# Controller_V2.net
KiCad netlist of a schematic drawn in Altium Designer
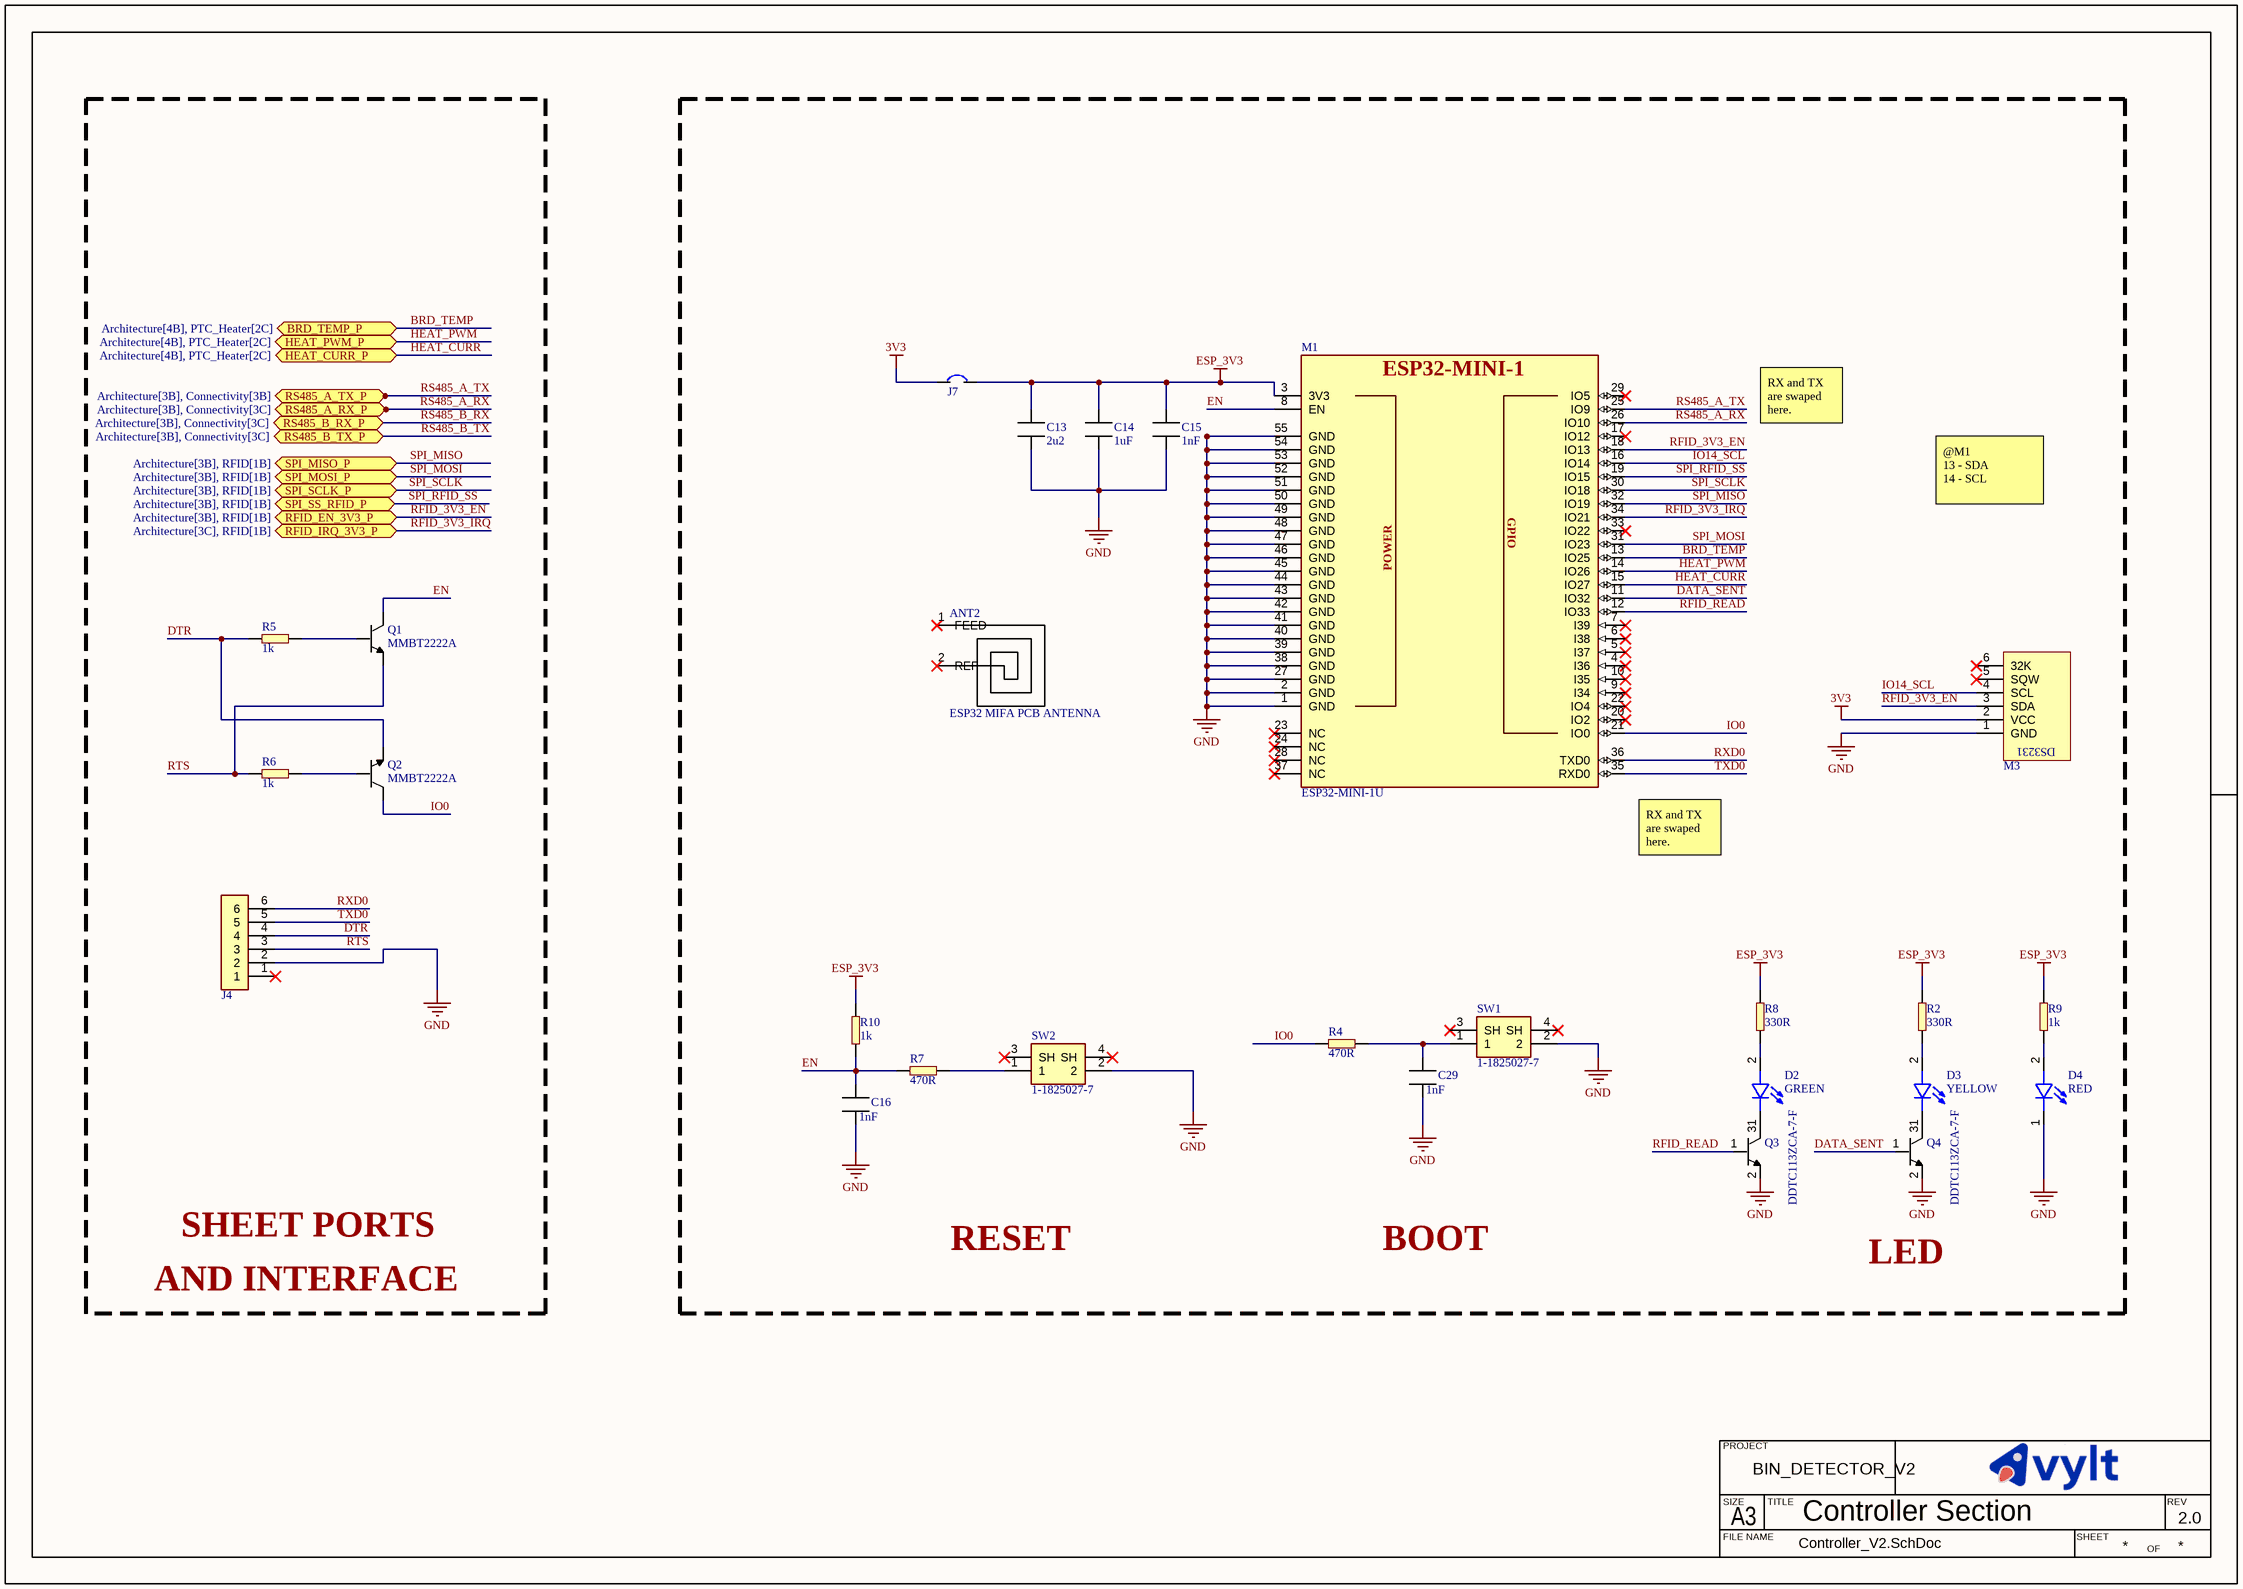
[diagram p0: Controller_V2.SchDoc]

(export (version "E")
  (design (tool "Eeschema 10.0.6"))
  (components
    (comp (ref "ANT2")
      (value "ESP32 MIFA PCB ANTENNA")
      (footprint "ESP32 MIFA PCB ANTENNA")
      (libsource (lib "Antenna") (part "ESP32 MIFA PCB ANTENNA"))
    )
    (comp (ref "C13")
      (value "2u2")
      (footprint "CAPC1608X10N")
      (description "MLCC 0603")
      (fields (field (name "Comment") "ERP_102-1"))
      (libsource (lib "Capacitor") (part "MLCC_0603"))
    )
    (comp (ref "C14")
      (value "1uF")
      (footprint "CAPC1608X10N")
      (description "MLCC 0603")
      (fields (field (name "Comment") "ERP_102-1"))
      (libsource (lib "Capacitor") (part "MLCC_0603"))
    )
    (comp (ref "C15")
      (value "1nF")
      (footprint "CAPC1608X10N")
      (description "MLCC 0603")
      (fields (field (name "Comment") "ERP_102-1"))
      (libsource (lib "Capacitor") (part "MLCC_0603"))
    )
    (comp (ref "C16")
      (value "1nF")
      (footprint "CAPC1608X10N")
      (description "MLCC 0603")
      (fields (field (name "Comment") "ERP_102-1"))
      (libsource (lib "Capacitor") (part "MLCC_0603"))
    )
    (comp (ref "C29")
      (value "1nF")
      (footprint "CAPC1608X10N")
      (description "MLCC 0603")
      (fields (field (name "Comment") "ERP_102-1"))
      (libsource (lib "Capacitor") (part "MLCC_0603"))
    )
    (comp (ref "D2")
      (value "GREEN")
      (footprint "LED_2SMD")
      (description "LED GREEN CLEAR 1204 SMD R/A")
      (fields (field (name "Comment") "LED_2SMD"))
      (libsource (lib "LED") (part "LED_2SMD"))
    )
    (comp (ref "D3")
      (value "YELLOW")
      (footprint "LED_2SMD")
      (description "LED YELLOW CLEAR 1204 SMD R/A")
      (fields (field (name "Comment") "LED_2SMD"))
      (libsource (lib "LED") (part "LED_2SMD"))
    )
    (comp (ref "D4")
      (value "RED")
      (footprint "LED_2SMD")
      (description "LED RED CLEAR 1204 SMD R/A")
      (fields (field (name "Comment") "LED_2SMD"))
      (libsource (lib "LED") (part "LED_2SMD"))
    )
    (comp (ref "J4")
      (value "ERP_148-2")
      (footprint "6PX1R")
      (description "6PX1R")
      (libsource (lib "Male_Header_P2.54") (part "6PX1R"))
    )
    (comp (ref "J7")
      (value "Jumper_2P")
      (footprint "Jumper_2P")
      (description "Jumper 2 Pins")
      (libsource (lib "Jumper") (part "Jumper_2P"))
    )
    (comp (ref "M1")
      (value "ESP32-MINI-1U")
      (footprint "ESP32_MINI_1U")
      (description "ESP32_C3_MINI_1 Module")
      (fields (field (name "Comment") "ERP_140-3"))
      (libsource (lib "ESP") (part "ESP32_MINI_1"))
    )
    (comp (ref "M3")
      (value "DS3231_HW-084")
      (footprint "DS3231_HW-084")
      (description "DS3231 Time Module , HW-084")
      (libsource (lib "Time") (part "DS3231_HW-084"))
    )
    (comp (ref "Q1")
      (value "MMBT2222A")
      (footprint "MMBT2222")
      (fields (field (name "Comment") "ERP_105-1"))
      (libsource (lib "BJT") (part "MMBT2222"))
    )
    (comp (ref "Q2")
      (value "MMBT2222A")
      (footprint "MMBT2222")
      (fields (field (name "Comment") "ERP_105-1"))
      (libsource (lib "BJT") (part "MMBT2222"))
    )
    (comp (ref "Q3")
      (value "DDTC113ZCA-7-F")
      (footprint "DDTCXXXXCA")
      (description "TRANS PREBIAS NPN 50V SOT23-3")
      (fields (field (name "Comment") "ERP_105-1"))
      (libsource (lib "BJT") (part "DDTCXXXXCA"))
    )
    (comp (ref "Q4")
      (value "DDTC113ZCA-7-F")
      (footprint "DDTCXXXXCA")
      (description "TRANS PREBIAS NPN 50V SOT23-3")
      (fields (field (name "Comment") "ERP_105-1"))
      (libsource (lib "BJT") (part "DDTCXXXXCA"))
    )
    (comp (ref "R2")
      (value "330R")
      (footprint "RES_0603")
      (description "RES_0603")
      (fields (field (name "Comment") "ERP_101-1"))
      (libsource (lib "") (part "RES_0603_1"))
    )
    (comp (ref "R4")
      (value "470R")
      (footprint "RES_0603")
      (description "RES_0603")
      (fields (field (name "Comment") "ERP_101-1"))
      (libsource (lib "Resistor") (part "RES_0603"))
    )
    (comp (ref "R5")
      (value "1k")
      (footprint "RES_0603")
      (description "RES_0603")
      (fields (field (name "Comment") "ERP_101-1"))
      (libsource (lib "Resistor") (part "RES_0603"))
    )
    (comp (ref "R6")
      (value "1k")
      (footprint "RES_0603")
      (description "RES_0603")
      (fields (field (name "Comment") "ERP_101-1"))
      (libsource (lib "Resistor") (part "RES_0603"))
    )
    (comp (ref "R7")
      (value "470R")
      (footprint "RES_0603")
      (description "RES_0603")
      (fields (field (name "Comment") "ERP_101-1"))
      (libsource (lib "Resistor") (part "RES_0603"))
    )
    (comp (ref "R8")
      (value "330R")
      (footprint "RES_0603")
      (description "RES_0603")
      (fields (field (name "Comment") "ERP_101-1"))
      (libsource (lib "") (part "RES_0603_1"))
    )
    (comp (ref "R9")
      (value "1k")
      (footprint "RES_0603")
      (description "RES_0603")
      (fields (field (name "Comment") "ERP_101-1"))
      (libsource (lib "") (part "RES_0603_1"))
    )
    (comp (ref "R10")
      (value "1k")
      (footprint "RES_0603")
      (description "RES_0603")
      (fields (field (name "Comment") "ERP_101-1"))
      (libsource (lib "") (part "RES_0603_1"))
    )
    (comp (ref "SW1")
      (value "1-1825027-7")
      (footprint "FSM_6X6")
      (fields (field (name "Comment") "ERP_110-4"))
      (libsource (lib "Switch") (part "FSM_6X6"))
    )
    (comp (ref "SW2")
      (value "1-1825027-7")
      (footprint "FSM_6X6")
      (fields (field (name "Comment") "ERP_110-4"))
      (libsource (lib "Switch") (part "FSM_6X6"))
    )
  )
  (nets
    (net (code "2") (name "/BRD_TEMP") (class "Default")
      (node (ref "M1") (pin "13") (pinfunction "IO25_13") (pintype "bidirectional"))
    )
    (net (code "3") (name "/DATA_SENT") (class "Default")
      (node (ref "M1") (pin "11") (pinfunction "IO32_11") (pintype "bidirectional"))
      (node (ref "Q4") (pin "1") (pinfunction "1_1") (pintype "passive"))
    )
    (net (code "4") (name "/DTR") (class "Default")
      (node (ref "J4") (pin "4") (pinfunction "4_4") (pintype "passive"))
      (node (ref "Q2") (pin "2") (pinfunction "2_2") (pintype "passive"))
      (node (ref "R5") (pin "2") (pinfunction "2_2") (pintype "passive"))
    )
    (net (code "5") (name "/EN") (class "Default")
      (node (ref "C16") (pin "1") (pinfunction "1_1") (pintype "passive"))
      (node (ref "M1") (pin "8") (pinfunction "EN_8") (pintype "passive"))
      (node (ref "Q1") (pin "3") (pinfunction "3_3") (pintype "passive"))
      (node (ref "R10") (pin "1") (pinfunction "1_1") (pintype "passive"))
      (node (ref "R7") (pin "2") (pinfunction "2_2") (pintype "passive"))
    )
    (net (code "6") (name "/HEAT_CURR") (class "Default")
      (node (ref "M1") (pin "15") (pinfunction "IO27_15") (pintype "bidirectional"))
    )
    (net (code "7") (name "/HEAT_PWM") (class "Default")
      (node (ref "M1") (pin "14") (pinfunction "IO26_14") (pintype "bidirectional"))
    )
    (net (code "8") (name "/IO0") (class "Default")
      (node (ref "M1") (pin "21") (pinfunction "IO0_21") (pintype "bidirectional"))
      (node (ref "Q2") (pin "3") (pinfunction "3_3") (pintype "passive"))
      (node (ref "R4") (pin "2") (pinfunction "2_2") (pintype "passive"))
    )
    (net (code "9") (name "/IO14_SCL") (class "Default")
      (node (ref "M1") (pin "16") (pinfunction "IO14_16") (pintype "bidirectional"))
      (node (ref "M3") (pin "4") (pinfunction "SCL_4") (pintype "passive"))
    )
    (net (code "10") (name "/RFID_3V3_EN") (class "Default")
      (node (ref "M1") (pin "18") (pinfunction "IO13_18") (pintype "bidirectional"))
      (node (ref "M3") (pin "3") (pinfunction "SDA_3") (pintype "passive"))
    )
    (net (code "11") (name "/RFID_3V3_IRQ") (class "Default")
      (node (ref "M1") (pin "34") (pinfunction "IO21_34") (pintype "bidirectional"))
    )
    (net (code "12") (name "/RFID_READ") (class "Default")
      (node (ref "M1") (pin "12") (pinfunction "IO33_12") (pintype "bidirectional"))
      (node (ref "Q3") (pin "1") (pinfunction "1_1") (pintype "passive"))
    )
    (net (code "13") (name "/RS485_A_RX") (class "Default")
      (node (ref "M1") (pin "26") (pinfunction "IO10_26") (pintype "bidirectional"))
    )
    (net (code "14") (name "/RS485_A_TX") (class "Default")
      (node (ref "M1") (pin "25") (pinfunction "IO9_25") (pintype "bidirectional"))
    )
    (net (code "17") (name "/RTS") (class "Default")
      (node (ref "J4") (pin "3") (pinfunction "3_3") (pintype "passive"))
      (node (ref "Q1") (pin "2") (pinfunction "2_2") (pintype "passive"))
      (node (ref "R6") (pin "2") (pinfunction "2_2") (pintype "passive"))
    )
    (net (code "18") (name "/RXD0") (class "Default")
      (node (ref "J4") (pin "6") (pinfunction "6_6") (pintype "passive"))
      (node (ref "M1") (pin "36") (pinfunction "TXD0_36") (pintype "bidirectional"))
    )
    (net (code "19") (name "/SPI_MISO") (class "Default")
      (node (ref "M1") (pin "32") (pinfunction "IO19_32") (pintype "bidirectional"))
    )
    (net (code "20") (name "/SPI_MOSI") (class "Default")
      (node (ref "M1") (pin "31") (pinfunction "IO23_31") (pintype "bidirectional"))
    )
    (net (code "21") (name "/SPI_RFID_SS") (class "Default")
      (node (ref "M1") (pin "19") (pinfunction "IO15_19") (pintype "bidirectional"))
    )
    (net (code "22") (name "/SPI_SCLK") (class "Default")
      (node (ref "M1") (pin "30") (pinfunction "IO18_30") (pintype "bidirectional"))
    )
    (net (code "23") (name "/TXD0") (class "Default")
      (node (ref "J4") (pin "5") (pinfunction "5_5") (pintype "passive"))
      (node (ref "M1") (pin "35") (pinfunction "RXD0_35") (pintype "bidirectional"))
    )
    (net (code "24") (name "3V3") (class "Default")
      (node (ref "J7") (pin "1") (pintype "passive"))
      (node (ref "M3") (pin "2") (pinfunction "VCC_2") (pintype "passive"))
    )
    (net (code "25") (name "ESP_3V3") (class "Default")
      (node (ref "C13") (pin "2") (pinfunction "2_2") (pintype "passive"))
      (node (ref "C14") (pin "2") (pinfunction "2_2") (pintype "passive"))
      (node (ref "C15") (pin "2") (pinfunction "2_2") (pintype "passive"))
      (node (ref "J7") (pin "2") (pintype "passive"))
      (node (ref "M1") (pin "3") (pinfunction "3V3_3") (pintype "power_in"))
      (node (ref "R10") (pin "2") (pinfunction "2_2") (pintype "passive"))
      (node (ref "R2") (pin "2") (pinfunction "2_2") (pintype "passive"))
      (node (ref "R8") (pin "2") (pinfunction "2_2") (pintype "passive"))
      (node (ref "R9") (pin "2") (pinfunction "2_2") (pintype "passive"))
    )
    (net (code "26") (name "GND") (class "Default")
      (node (ref "C13") (pin "1") (pinfunction "1_1") (pintype "passive"))
      (node (ref "C14") (pin "1") (pinfunction "1_1") (pintype "passive"))
      (node (ref "C15") (pin "1") (pinfunction "1_1") (pintype "passive"))
      (node (ref "C16") (pin "2") (pinfunction "2_2") (pintype "passive"))
      (node (ref "C29") (pin "2") (pinfunction "2_2") (pintype "passive"))
      (node (ref "D4") (pin "1") (pinfunction "1_1") (pintype "passive"))
      (node (ref "J4") (pin "2") (pinfunction "2_2") (pintype "passive"))
      (node (ref "M1") (pin "1") (pinfunction "GND_1") (pintype "passive"))
      (node (ref "M1") (pin "2") (pinfunction "GND_2") (pintype "passive"))
      (node (ref "M1") (pin "27") (pinfunction "GND_27") (pintype "passive"))
      (node (ref "M1") (pin "38") (pinfunction "GND_38") (pintype "passive"))
      (node (ref "M1") (pin "39") (pinfunction "GND_39") (pintype "passive"))
      (node (ref "M1") (pin "40") (pinfunction "GND_40") (pintype "passive"))
      (node (ref "M1") (pin "41") (pinfunction "GND_41") (pintype "passive"))
      (node (ref "M1") (pin "42") (pinfunction "GND_42") (pintype "passive"))
      (node (ref "M1") (pin "43") (pinfunction "GND_43") (pintype "passive"))
      (node (ref "M1") (pin "44") (pinfunction "GND_44") (pintype "passive"))
      (node (ref "M1") (pin "45") (pinfunction "GND_45") (pintype "passive"))
      (node (ref "M1") (pin "46") (pinfunction "GND_46") (pintype "passive"))
      (node (ref "M1") (pin "47") (pinfunction "GND_47") (pintype "passive"))
      (node (ref "M1") (pin "48") (pinfunction "GND_48") (pintype "passive"))
      (node (ref "M1") (pin "49") (pinfunction "GND_49") (pintype "passive"))
      (node (ref "M1") (pin "50") (pinfunction "GND_50") (pintype "passive"))
      (node (ref "M1") (pin "51") (pinfunction "GND_51") (pintype "passive"))
      (node (ref "M1") (pin "52") (pinfunction "GND_52") (pintype "passive"))
      (node (ref "M1") (pin "53") (pinfunction "GND_53") (pintype "passive"))
      (node (ref "M1") (pin "54") (pinfunction "GND_54") (pintype "passive"))
      (node (ref "M1") (pin "55") (pinfunction "GND_55") (pintype "passive"))
      (node (ref "M3") (pin "1") (pinfunction "GND_1") (pintype "passive"))
      (node (ref "Q3") (pin "2") (pinfunction "2_2") (pintype "passive"))
      (node (ref "Q4") (pin "2") (pinfunction "2_2") (pintype "passive"))
      (node (ref "SW1") (pin "2") (pinfunction "2_2") (pintype "passive"))
      (node (ref "SW2") (pin "2") (pinfunction "2_2") (pintype "passive"))
    )
    (net (code "27") (name "Net-(C29-Pad1)") (class "Default")
      (node (ref "C29") (pin "1") (pinfunction "1_1") (pintype "passive"))
      (node (ref "R4") (pin "1") (pinfunction "1_1") (pintype "passive"))
      (node (ref "SW1") (pin "1") (pinfunction "1_1") (pintype "passive"))
    )
    (net (code "28") (name "Net-(D2-Pad1)") (class "Default")
      (node (ref "D2") (pin "1") (pinfunction "1_1") (pintype "passive"))
      (node (ref "Q3") (pin "3") (pinfunction "3_3") (pintype "passive"))
    )
    (net (code "29") (name "Net-(D2-Pad2)") (class "Default")
      (node (ref "D2") (pin "2") (pinfunction "2_2") (pintype "passive"))
      (node (ref "R8") (pin "1") (pinfunction "1_1") (pintype "passive"))
    )
    (net (code "30") (name "Net-(D3-Pad1)") (class "Default")
      (node (ref "D3") (pin "1") (pinfunction "1_1") (pintype "passive"))
      (node (ref "Q4") (pin "3") (pinfunction "3_3") (pintype "passive"))
    )
    (net (code "31") (name "Net-(D3-Pad2)") (class "Default")
      (node (ref "D3") (pin "2") (pinfunction "2_2") (pintype "passive"))
      (node (ref "R2") (pin "1") (pinfunction "1_1") (pintype "passive"))
    )
    (net (code "32") (name "Net-(D4-Pad2)") (class "Default")
      (node (ref "D4") (pin "2") (pinfunction "2_2") (pintype "passive"))
      (node (ref "R9") (pin "1") (pinfunction "1_1") (pintype "passive"))
    )
    (net (code "33") (name "Net-(Q1-Pad1)") (class "Default")
      (node (ref "Q1") (pin "1") (pinfunction "1_1") (pintype "passive"))
      (node (ref "R5") (pin "1") (pinfunction "1_1") (pintype "passive"))
    )
    (net (code "34") (name "Net-(Q2-Pad1)") (class "Default")
      (node (ref "Q2") (pin "1") (pinfunction "1_1") (pintype "passive"))
      (node (ref "R6") (pin "1") (pinfunction "1_1") (pintype "passive"))
    )
    (net (code "35") (name "Net-(R7-Pad1)") (class "Default")
      (node (ref "R7") (pin "1") (pinfunction "1_1") (pintype "passive"))
      (node (ref "SW2") (pin "1") (pinfunction "1_1") (pintype "passive"))
    )
    (net (code "36") (name "unconnected-(ANT2-FEED-Pad1)") (class "Default")
      (node (ref "ANT2") (pin "1") (pinfunction "FEED_1") (pintype "passive+no_connect"))
    )
    (net (code "37") (name "unconnected-(ANT2-REF-Pad2)") (class "Default")
      (node (ref "ANT2") (pin "2") (pinfunction "REF_2") (pintype "passive+no_connect"))
    )
    (net (code "38") (name "unconnected-(J4-Pad1)") (class "Default")
      (node (ref "J4") (pin "1") (pinfunction "1_1") (pintype "passive+no_connect"))
    )
    (net (code "39") (name "unconnected-(M1-I34-Pad9)") (class "Default")
      (node (ref "M1") (pin "9") (pinfunction "I34_9") (pintype "input+no_connect"))
    )
    (net (code "40") (name "unconnected-(M1-I35-Pad10)") (class "Default")
      (node (ref "M1") (pin "10") (pinfunction "I35_10") (pintype "input+no_connect"))
    )
    (net (code "41") (name "unconnected-(M1-I36-Pad4)") (class "Default")
      (node (ref "M1") (pin "4") (pinfunction "I36_4") (pintype "input+no_connect"))
    )
    (net (code "42") (name "unconnected-(M1-I37-Pad5)") (class "Default")
      (node (ref "M1") (pin "5") (pinfunction "I37_5") (pintype "input+no_connect"))
    )
    (net (code "43") (name "unconnected-(M1-I38-Pad6)") (class "Default")
      (node (ref "M1") (pin "6") (pinfunction "I38_6") (pintype "input+no_connect"))
    )
    (net (code "44") (name "unconnected-(M1-I39-Pad7)") (class "Default")
      (node (ref "M1") (pin "7") (pinfunction "I39_7") (pintype "input+no_connect"))
    )
    (net (code "45") (name "unconnected-(M1-IO2-Pad20)") (class "Default")
      (node (ref "M1") (pin "20") (pinfunction "IO2_20") (pintype "bidirectional+no_connect"))
    )
    (net (code "46") (name "unconnected-(M1-IO4-Pad22)") (class "Default")
      (node (ref "M1") (pin "22") (pinfunction "IO4_22") (pintype "bidirectional+no_connect"))
    )
    (net (code "47") (name "unconnected-(M1-IO5-Pad29)") (class "Default")
      (node (ref "M1") (pin "29") (pinfunction "IO5_29") (pintype "bidirectional+no_connect"))
    )
    (net (code "48") (name "unconnected-(M1-IO12-Pad17)") (class "Default")
      (node (ref "M1") (pin "17") (pinfunction "IO12_17") (pintype "bidirectional+no_connect"))
    )
    (net (code "49") (name "unconnected-(M1-IO22-Pad33)") (class "Default")
      (node (ref "M1") (pin "33") (pinfunction "IO22_33") (pintype "bidirectional+no_connect"))
    )
    (net (code "50") (name "unconnected-(M1-NC-Pad23)") (class "Default")
      (node (ref "M1") (pin "23") (pinfunction "NC_23") (pintype "passive+no_connect"))
    )
    (net (code "51") (name "unconnected-(M1-NC-Pad24)") (class "Default")
      (node (ref "M1") (pin "24") (pinfunction "NC_24") (pintype "passive+no_connect"))
    )
    (net (code "52") (name "unconnected-(M1-NC-Pad28)") (class "Default")
      (node (ref "M1") (pin "28") (pinfunction "NC_28") (pintype "passive+no_connect"))
    )
    (net (code "53") (name "unconnected-(M1-NC-Pad37)") (class "Default")
      (node (ref "M1") (pin "37") (pinfunction "NC_37") (pintype "passive+no_connect"))
    )
    (net (code "54") (name "unconnected-(M3-32K-Pad6)") (class "Default")
      (node (ref "M3") (pin "6") (pinfunction "32K_6") (pintype "passive+no_connect"))
    )
    (net (code "55") (name "unconnected-(M3-SQW-Pad5)") (class "Default")
      (node (ref "M3") (pin "5") (pinfunction "SQW_5") (pintype "passive+no_connect"))
    )
    (net (code "56") (name "unconnected-(SW1-SH-Pad3)") (class "Default")
      (node (ref "SW1") (pin "3") (pinfunction "SH_3") (pintype "passive+no_connect"))
    )
    (net (code "57") (name "unconnected-(SW1-SH-Pad4)") (class "Default")
      (node (ref "SW1") (pin "4") (pinfunction "SH_4") (pintype "passive+no_connect"))
    )
    (net (code "58") (name "unconnected-(SW2-SH-Pad3)") (class "Default")
      (node (ref "SW2") (pin "3") (pinfunction "SH_3") (pintype "passive+no_connect"))
    )
    (net (code "59") (name "unconnected-(SW2-SH-Pad4)") (class "Default")
      (node (ref "SW2") (pin "4") (pinfunction "SH_4") (pintype "passive+no_connect"))
    )
  )
)
